# IO_Converter.net
KiCad netlist of a schematic drawn in Altium Designer
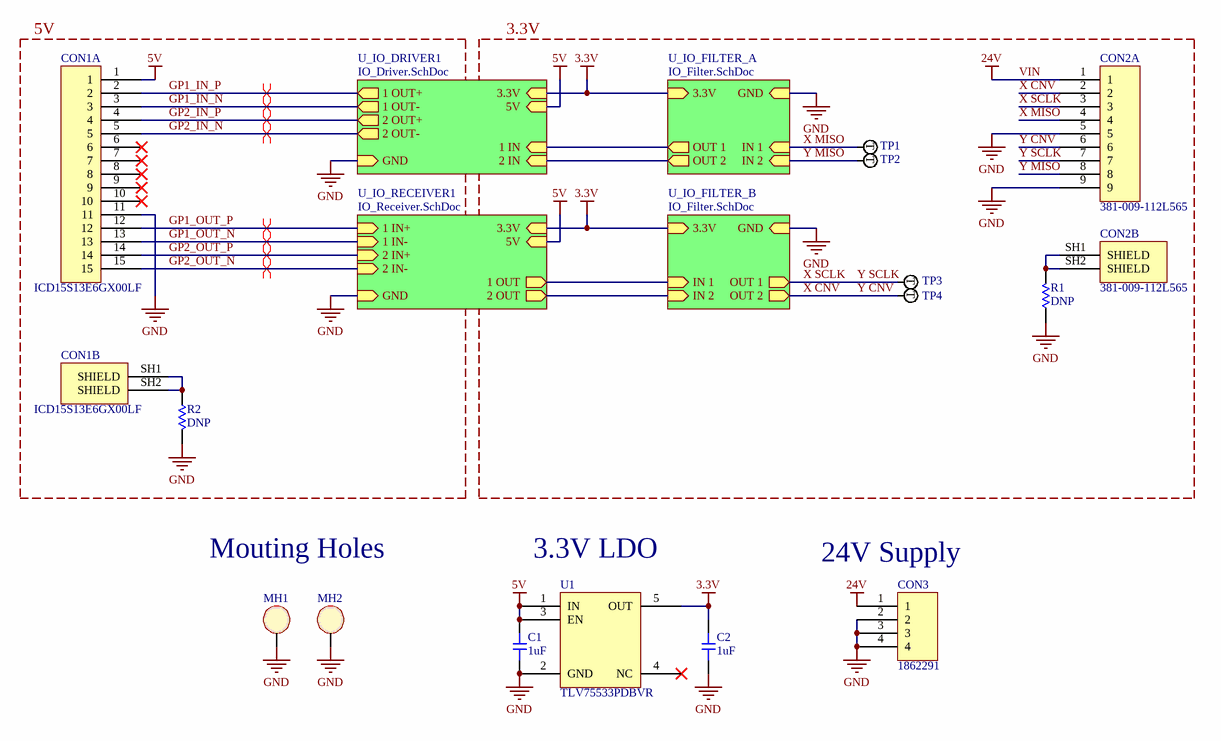
[diagram p0: IO_Converter.SchDoc]

(export (version "E")
  (design (tool "Eeschema 10.0.6"))
  (components
    (comp (ref "C1")
      (value "1uF")
      (footprint "0603-CAP")
      (description "CAP CER 1UF 10V X5R 0603")
      (fields (field (name "Comment") "CL10A105KP8NNWC"))
      (libsource (lib "IO_Converter") (part "Capacitor 1uF"))
    )
    (comp (ref "C2")
      (value "1uF")
      (footprint "0603-CAP")
      (description "CAP CER 1UF 10V X5R 0603")
      (fields (field (name "Comment") "CL10A105KP8NNWC"))
      (libsource (lib "IO_Converter") (part "Capacitor 1uF"))
    )
    (comp (ref "CON1")
      (value "ICD15S13E6GX00LF")
      (footprint "ICD15S13E6GX00LF")
      (description "15 Position D-Sub, High Density Receptacle, Female Sockets Connector")
      (libsource (lib "CRAMB") (part "ICD15S13E6GX00LF"))
    )
    (comp (ref "CON2")
      (value "381-009-112L565")
      (footprint "381-009-112L565")
      (description "9 Position D-Type, Micro-D Plug, Male Pins Connector")
      (libsource (lib "IO_Converter") (part "381-009-112L565"))
    )
    (comp (ref "CON3")
      (value "1862291")
      (footprint "1862291")
      (description "TERM BLOCK 4POS 45DEG 5MM PCB")
      (libsource (lib "IO_Converter") (part "1862291"))
    )
    (comp (ref "MH1")
      (value "MOUNT_HOLE")
      (footprint "MOUNTING_HOLE")
      (description "MOUNTING HOLE")
      (libsource (lib "IO_Converter") (part "MOUNT_HOLE"))
    )
    (comp (ref "MH2")
      (value "MOUNT_HOLE")
      (footprint "MOUNTING_HOLE")
      (description "MOUNTING HOLE")
      (libsource (lib "IO_Converter") (part "MOUNT_HOLE"))
    )
    (comp (ref "R1")
      (value "DNP")
      (footprint "0603-RES")
      (fields (field (name "Comment") "Resistor"))
      (libsource (lib "CRAMB") (part "Resistor"))
    )
    (comp (ref "R2")
      (value "DNP")
      (footprint "0603-RES")
      (fields (field (name "Comment") "Resistor"))
      (libsource (lib "CRAMB") (part "Resistor"))
    )
    (comp (ref "TP1")
      (value "RCU-0C")
      (footprint "RCU-0C")
      (description "PC TEST POINT NATURAL")
      (libsource (lib "IO_Converter") (part "Test Point"))
    )
    (comp (ref "TP2")
      (value "RCU-0C")
      (footprint "RCU-0C")
      (description "PC TEST POINT NATURAL")
      (libsource (lib "IO_Converter") (part "Test Point"))
    )
    (comp (ref "TP3")
      (value "RCU-0C")
      (footprint "RCU-0C")
      (description "PC TEST POINT NATURAL")
      (libsource (lib "IO_Converter") (part "Test Point"))
    )
    (comp (ref "TP4")
      (value "RCU-0C")
      (footprint "RCU-0C")
      (description "PC TEST POINT NATURAL")
      (libsource (lib "IO_Converter") (part "Test Point"))
    )
    (comp (ref "U1")
      (value "TLV75533PDBVR")
      (footprint "SOT95P280X145-5N")
      (description "IC REG LINEAR 3.3V 500MA SOT23-5")
      (libsource (lib "IO_Converter") (part "TLV75533PDBVR"))
    )
  )
  (nets
    (net (code "3") (name "/GP1_IN_N") (class "Default")
      (node (ref "CON1") (pin "3") (pinfunction "3_3") (pintype "passive"))
    )
    (net (code "4") (name "/GP1_IN_P") (class "Default")
      (node (ref "CON1") (pin "2") (pinfunction "2_2") (pintype "passive"))
    )
    (net (code "5") (name "/GP1_OUT_N") (class "Default")
      (node (ref "CON1") (pin "13") (pinfunction "13_13") (pintype "passive"))
    )
    (net (code "6") (name "/GP1_OUT_P") (class "Default")
      (node (ref "CON1") (pin "12") (pinfunction "12_12") (pintype "passive"))
    )
    (net (code "7") (name "/GP2_IN_N") (class "Default")
      (node (ref "CON1") (pin "5") (pinfunction "5_5") (pintype "passive"))
    )
    (net (code "8") (name "/GP2_IN_P") (class "Default")
      (node (ref "CON1") (pin "4") (pinfunction "4_4") (pintype "passive"))
    )
    (net (code "9") (name "/GP2_OUT_N") (class "Default")
      (node (ref "CON1") (pin "15") (pinfunction "15_15") (pintype "passive"))
    )
    (net (code "10") (name "/GP2_OUT_P") (class "Default")
      (node (ref "CON1") (pin "14") (pinfunction "14_14") (pintype "passive"))
    )
    (net (code "13") (name "/X CNV") (class "Default")
      (node (ref "CON2") (pin "2") (pinfunction "2_2") (pintype "passive"))
      (node (ref "CON2") (pin "6") (pinfunction "6_6") (pintype "passive"))
      (node (ref "TP4") (pin "1") (pinfunction "1_1") (pintype "passive"))
    )
    (net (code "14") (name "/X MISO") (class "Default")
      (node (ref "CON2") (pin "4") (pinfunction "4_4") (pintype "passive"))
      (node (ref "TP1") (pin "1") (pinfunction "1_1") (pintype "passive"))
    )
    (net (code "15") (name "/X SCLK") (class "Default")
      (node (ref "CON2") (pin "3") (pinfunction "3_3") (pintype "passive"))
      (node (ref "CON2") (pin "7") (pinfunction "7_7") (pintype "passive"))
      (node (ref "TP3") (pin "1") (pinfunction "1_1") (pintype "passive"))
    )
    (net (code "16") (name "/Y MISO") (class "Default")
      (node (ref "CON2") (pin "8") (pinfunction "8_8") (pintype "passive"))
      (node (ref "TP2") (pin "1") (pinfunction "1_1") (pintype "passive"))
    )
    (net (code "17") (name "3.3V") (class "Default")
      (node (ref "C2") (pin "2") (pinfunction "2_2") (pintype "passive"))
      (node (ref "U1") (pin "5") (pinfunction "OUT_5") (pintype "passive"))
    )
    (net (code "18") (name "5V") (class "Default")
      (node (ref "C1") (pin "2") (pinfunction "2_2") (pintype "passive"))
      (node (ref "CON1") (pin "1") (pinfunction "1_1") (pintype "passive"))
      (node (ref "U1") (pin "1") (pinfunction "IN_1") (pintype "passive"))
      (node (ref "U1") (pin "3") (pinfunction "EN_3") (pintype "passive"))
    )
    (net (code "19") (name "24V") (class "Default")
      (node (ref "CON2") (pin "1") (pinfunction "1_1") (pintype "passive"))
      (node (ref "CON3") (pin "1") (pinfunction "1_1") (pintype "passive"))
    )
    (net (code "20") (name "GND") (class "Default")
      (node (ref "C1") (pin "1") (pinfunction "1_1") (pintype "passive"))
      (node (ref "C2") (pin "1") (pinfunction "1_1") (pintype "passive"))
      (node (ref "CON1") (pin "11") (pinfunction "11_11") (pintype "passive"))
      (node (ref "CON2") (pin "5") (pinfunction "5_5") (pintype "passive"))
      (node (ref "CON2") (pin "9") (pinfunction "9_9") (pintype "passive"))
      (node (ref "CON3") (pin "2") (pinfunction "2_2") (pintype "passive"))
      (node (ref "CON3") (pin "3") (pinfunction "3_3") (pintype "passive"))
      (node (ref "CON3") (pin "4") (pinfunction "4_4") (pintype "passive"))
      (node (ref "MH1") (pin "1") (pinfunction "1_1") (pintype "passive"))
      (node (ref "MH2") (pin "1") (pinfunction "1_1") (pintype "passive"))
      (node (ref "R1") (pin "2") (pinfunction "2_2") (pintype "passive"))
      (node (ref "R2") (pin "2") (pinfunction "2_2") (pintype "passive"))
      (node (ref "U1") (pin "2") (pinfunction "GND_2") (pintype "passive"))
    )
    (net (code "21") (name "Net-(CON1B-SHIELD-PadSH1)") (class "Default")
      (node (ref "CON1") (pin "SH1") (pinfunction "SHIELD_SH1") (pintype "passive"))
      (node (ref "CON1") (pin "SH2") (pinfunction "SHIELD_SH2") (pintype "passive"))
      (node (ref "R2") (pin "1") (pinfunction "1_1") (pintype "passive"))
    )
    (net (code "22") (name "Net-(CON2B-SHIELD-PadSH1)") (class "Default")
      (node (ref "CON2") (pin "SH1") (pinfunction "SHIELD_SH1") (pintype "passive"))
      (node (ref "CON2") (pin "SH2") (pinfunction "SHIELD_SH2") (pintype "passive"))
      (node (ref "R1") (pin "1") (pinfunction "1_1") (pintype "passive"))
    )
    (net (code "23") (name "unconnected-(CON1-Pad6)") (class "Default")
      (node (ref "CON1") (pin "6") (pinfunction "6_6") (pintype "passive+no_connect"))
    )
    (net (code "24") (name "unconnected-(CON1-Pad7)") (class "Default")
      (node (ref "CON1") (pin "7") (pinfunction "7_7") (pintype "passive+no_connect"))
    )
    (net (code "25") (name "unconnected-(CON1-Pad8)") (class "Default")
      (node (ref "CON1") (pin "8") (pinfunction "8_8") (pintype "passive+no_connect"))
    )
    (net (code "26") (name "unconnected-(CON1-Pad9)") (class "Default")
      (node (ref "CON1") (pin "9") (pinfunction "9_9") (pintype "passive+no_connect"))
    )
    (net (code "27") (name "unconnected-(CON1-Pad10)") (class "Default")
      (node (ref "CON1") (pin "10") (pinfunction "10_10") (pintype "passive+no_connect"))
    )
    (net (code "28") (name "unconnected-(U1-NC-Pad4)") (class "Default")
      (node (ref "U1") (pin "4") (pinfunction "NC_4") (pintype "passive+no_connect"))
    )
  )
)
